# Main.net
KiCad netlist of a schematic drawn in Altium Designer
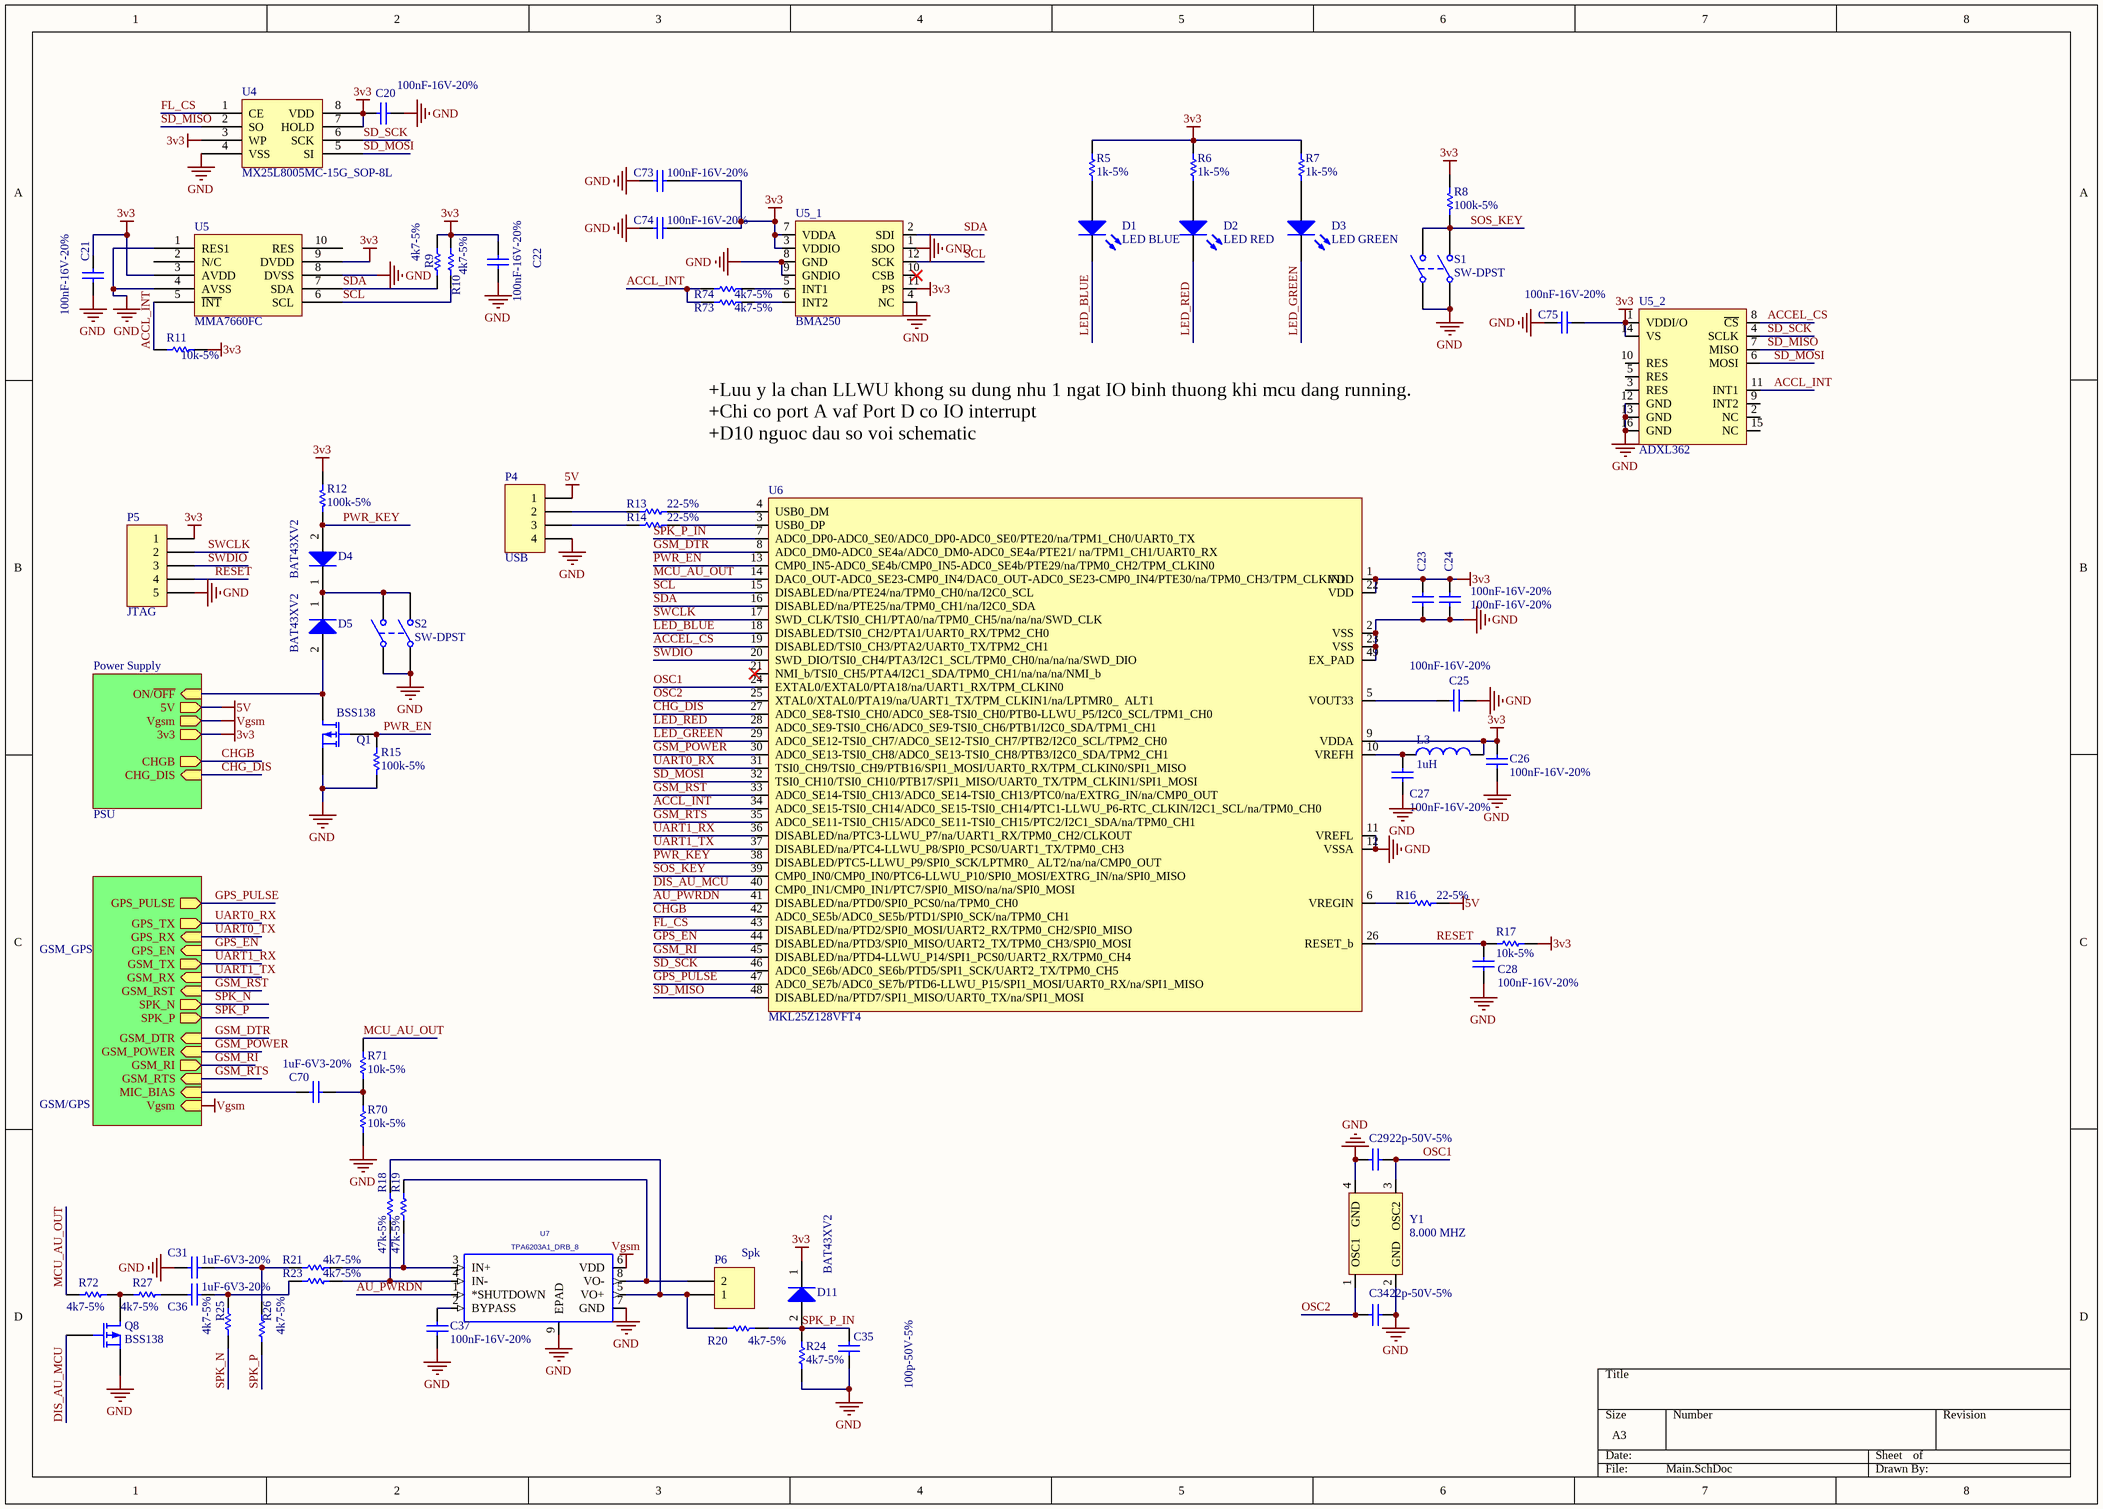
[diagram p0: Main.SchDoc]

(export (version "E")
  (design (tool "Eeschema 10.0.6"))
  (components
    (comp (ref "C20")
      (value "100nF-16V-20%")
      (footprint "C0402")
      (description "CAP CER 0.1UF 16V Y5V 0402")
      (fields
        (field (name "MANUFACTURER") "Yageo")
        (field (name "DIGI-KEY PART NUMBER") "311-1047-1-ND")
        (field (name "PUBLISHER") "Altium Limited")
      )
      (libsource (lib "Miscellaneous Devices") (part "Cap"))
    )
    (comp (ref "C21")
      (value "100nF-16V-20%")
      (footprint "C0402")
      (description "CAP CER 0.1UF 16V Y5V 0402")
      (fields
        (field (name "MANUFACTURER") "Yageo")
        (field (name "DIGI-KEY PART NUMBER") "311-1047-1-ND")
        (field (name "PUBLISHER") "Altium Limited")
      )
      (libsource (lib "Miscellaneous Devices") (part "Cap"))
    )
    (comp (ref "C22")
      (value "100nF-16V-20%")
      (footprint "C0402")
      (description "CAP CER 0.1UF 16V Y5V 0402")
      (fields
        (field (name "MANUFACTURER") "Yageo")
        (field (name "DIGI-KEY PART NUMBER") "311-1047-1-ND")
        (field (name "PUBLISHER") "Altium Limited")
      )
      (libsource (lib "Miscellaneous Devices") (part "Cap"))
    )
    (comp (ref "C23")
      (value "100nF-16V-20%")
      (footprint "C0402")
      (description "CAP CER 0.1UF 16V Y5V 0402")
      (fields
        (field (name "MANUFACTURER") "Yageo")
        (field (name "DIGI-KEY PART NUMBER") "311-1047-1-ND")
        (field (name "PUBLISHER") "Altium Limited")
      )
      (libsource (lib "Miscellaneous Devices") (part "Cap"))
    )
    (comp (ref "C24")
      (value "100nF-16V-20%")
      (footprint "C0402")
      (description "CAP CER 0.1UF 16V Y5V 0402")
      (fields
        (field (name "MANUFACTURER") "Yageo")
        (field (name "DIGI-KEY PART NUMBER") "311-1047-1-ND")
        (field (name "PUBLISHER") "Altium Limited")
      )
      (libsource (lib "Miscellaneous Devices") (part "Cap"))
    )
    (comp (ref "C25")
      (value "100nF-16V-20%")
      (footprint "C0402")
      (description "CAP CER 0.1UF 16V Y5V 0402")
      (fields
        (field (name "MANUFACTURER") "Yageo")
        (field (name "DIGI-KEY PART NUMBER") "311-1047-1-ND")
        (field (name "PUBLISHER") "Altium Limited")
      )
      (libsource (lib "Miscellaneous Devices") (part "Cap"))
    )
    (comp (ref "C26")
      (value "100nF-16V-20%")
      (footprint "C0402")
      (description "CAP CER 0.1UF 16V Y5V 0402")
      (fields
        (field (name "MANUFACTURER") "Yageo")
        (field (name "DIGI-KEY PART NUMBER") "311-1047-1-ND")
        (field (name "PUBLISHER") "Altium Limited")
      )
      (libsource (lib "Miscellaneous Devices") (part "Cap"))
    )
    (comp (ref "C27")
      (value "100nF-16V-20%")
      (footprint "C0402")
      (description "CAP CER 0.1UF 16V Y5V 0402")
      (fields
        (field (name "MANUFACTURER") "Yageo")
        (field (name "DIGI-KEY PART NUMBER") "311-1047-1-ND")
        (field (name "PUBLISHER") "Altium Limited")
      )
      (libsource (lib "Miscellaneous Devices") (part "Cap"))
    )
    (comp (ref "C28")
      (value "100nF-16V-20%")
      (footprint "C0402")
      (description "CAP CER 0.1UF 16V Y5V 0402")
      (fields
        (field (name "MANUFACTURER") "Yageo")
        (field (name "DIGI-KEY PART NUMBER") "311-1047-1-ND")
        (field (name "PUBLISHER") "Altium Limited")
      )
      (libsource (lib "Miscellaneous Devices") (part "Cap"))
    )
    (comp (ref "C29")
      (value "22p-50V-5%")
      (footprint "C0402")
      (description "CAP CER 22PF 50V 5% NPO 0402")
      (fields
        (field (name "MANUFACTURER") "Yageo")
        (field (name "DIGI-KEY PART NUMBER") "311-1018-2-ND")
        (field (name "PUBLISHER") "Altium Limited")
      )
      (libsource (lib "Miscellaneous Devices") (part "Cap"))
    )
    (comp (ref "C31")
      (value "1uF-6V3-20%")
      (footprint "C0402")
      (description "CAP CER 1UF 6.3V Y5V 0402")
      (fields
        (field (name "MANUFACTURER") "Yageo")
        (field (name "DIGI-KEY PART NUMBER") "311-1377-2-ND")
        (field (name "PUBLISHER") "Altium Limited")
      )
      (libsource (lib "Miscellaneous Devices") (part "Cap"))
    )
    (comp (ref "C34")
      (value "22p-50V-5%")
      (footprint "C0402")
      (description "CAP CER 22PF 50V 5% NPO 0402")
      (fields
        (field (name "MANUFACTURER") "Yageo")
        (field (name "DIGI-KEY PART NUMBER") "311-1018-2-ND")
        (field (name "PUBLISHER") "Altium Limited")
      )
      (libsource (lib "Miscellaneous Devices") (part "Cap"))
    )
    (comp (ref "C35")
      (value "100p-50V-5%")
      (footprint "C0402")
      (description "CAP CER 100PF 50V 5% NPO 0402")
      (fields
        (field (name "MANUFACTURER") "Yageo")
        (field (name "DIGI-KEY PART NUMBER") "311-1024-2-ND")
        (field (name "PUBLISHER") "Altium Limited")
      )
      (libsource (lib "Miscellaneous Devices") (part "Cap"))
    )
    (comp (ref "C36")
      (value "1uF-6V3-20%")
      (footprint "C0402")
      (description "CAP CER 1UF 6.3V Y5V 0402")
      (fields
        (field (name "MANUFACTURER") "Yageo")
        (field (name "DIGI-KEY PART NUMBER") "311-1377-2-ND")
        (field (name "PUBLISHER") "Altium Limited")
      )
      (libsource (lib "Miscellaneous Devices") (part "Cap"))
    )
    (comp (ref "C37")
      (value "100nF-16V-20%")
      (footprint "C0402")
      (description "CAP CER 0.1UF 16V Y5V 0402")
      (fields
        (field (name "MANUFACTURER") "Yageo")
        (field (name "DIGI-KEY PART NUMBER") "311-1047-1-ND")
        (field (name "PUBLISHER") "Altium Limited")
      )
      (libsource (lib "Miscellaneous Devices") (part "Cap"))
    )
    (comp (ref "C70")
      (value "1uF-6V3-20%")
      (footprint "C0402")
      (description "CAP CER 1UF 6.3V Y5V 0402")
      (fields
        (field (name "MANUFACTURER") "Yageo")
        (field (name "DIGI-KEY PART NUMBER") "311-1377-2-ND")
        (field (name "PUBLISHER") "Altium Limited")
      )
      (libsource (lib "Miscellaneous Devices") (part "Cap"))
    )
    (comp (ref "C73")
      (value "100nF-16V-20%")
      (footprint "C0402")
      (description "CAP CER 0.1UF 16V Y5V 0402")
      (fields
        (field (name "MANUFACTURER") "Yageo")
        (field (name "DIGI-KEY PART NUMBER") "311-1047-1-ND")
        (field (name "PUBLISHER") "Altium Limited")
      )
      (libsource (lib "Miscellaneous Devices") (part "Cap"))
    )
    (comp (ref "C74")
      (value "100nF-16V-20%")
      (footprint "C0402")
      (description "CAP CER 0.1UF 16V Y5V 0402")
      (fields
        (field (name "MANUFACTURER") "Yageo")
        (field (name "DIGI-KEY PART NUMBER") "311-1047-1-ND")
        (field (name "PUBLISHER") "Altium Limited")
      )
      (libsource (lib "Miscellaneous Devices") (part "Cap"))
    )
    (comp (ref "C75")
      (value "100nF-16V-20%")
      (footprint "C0402")
      (description "CAP CER 0.1UF 16V Y5V 0402")
      (fields
        (field (name "MANUFACTURER") "Yageo")
        (field (name "DIGI-KEY PART NUMBER") "311-1047-1-ND")
        (field (name "PUBLISHER") "Altium Limited")
      )
      (libsource (lib "Miscellaneous Devices") (part "Cap"))
    )
    (comp (ref "D1")
      (value "LED BLUE")
      (footprint "LED0603-G")
      (description "LED BLUE CLEAR THIN 0603 SMD")
      (fields
        (field (name "DIGI-KEY PART NUMBER") "160-1446-2-ND")
        (field (name "MANUFACTURER") "Lite-On Inc")
        (field (name "PUBLISHER") "Altium Limited")
      )
      (libsource (lib "Miscellaneous Devices") (part "LED2"))
    )
    (comp (ref "D2")
      (value "LED RED")
      (footprint "LED0603-G")
      (description "LED RED CLEAR THIN 0603 SMD")
      (fields
        (field (name "DIGI-KEY PART NUMBER") "160-1446-2-ND")
        (field (name "MANUFACTURER") "Lite-On Inc")
        (field (name "PUBLISHER") "Altium Limited")
      )
      (libsource (lib "Miscellaneous Devices") (part "LED2"))
    )
    (comp (ref "D3")
      (value "LED GREEN")
      (footprint "LED0603-G")
      (description "LED GREEN CLEAR THIN 0603 SMD")
      (fields
        (field (name "DIGI-KEY PART NUMBER") "160-1446-2-ND")
        (field (name "MANUFACTURER") "Lite-On Inc")
        (field (name "PUBLISHER") "Altium Limited")
      )
      (libsource (lib "Miscellaneous Devices") (part "LED2"))
    )
    (comp (ref "D4")
      (value "BAT43XV2")
      (footprint "SOD-523F")
      (description "Diode Type SMD")
      (fields
        (field (name "DIGI-KEY PART NUMBER") "BAT43XV2CT-ND")
        (field (name "MANUFACTURER") "Fairchild Semiconductor")
        (field (name "PUBLISHER") "Altium Limited")
      )
      (libsource (lib "Miscellaneous Devices") (part "Diode"))
    )
    (comp (ref "D5")
      (value "BAT43XV2")
      (footprint "SOD-523F")
      (description "Diode Type SMD")
      (fields
        (field (name "DIGI-KEY PART NUMBER") "BAT43XV2CT-ND")
        (field (name "MANUFACTURER") "Fairchild Semiconductor")
        (field (name "PUBLISHER") "Altium Limited")
      )
      (libsource (lib "Miscellaneous Devices") (part "Diode"))
    )
    (comp (ref "D11")
      (value "BAT43XV2")
      (footprint "SOD-523F")
      (description "Diode Type SMD")
      (fields
        (field (name "DIGI-KEY PART NUMBER") "BAT43XV2CT-ND")
        (field (name "MANUFACTURER") "Fairchild Semiconductor")
        (field (name "PUBLISHER") "Altium Limited")
      )
      (libsource (lib "Miscellaneous Devices") (part "Diode"))
    )
    (comp (ref "L3")
      (value "1uH")
      (footprint "L0603")
      (description "INDUCTOR 1.0UH 150MA 0603")
      (fields
        (field (name "DIGI-KEY PART NUMBER") "490-4022-2-ND")
        (field (name "MANUFACTURER") "Murata Electronics North America")
        (field (name "PUBLISHER") "Altium Limited")
      )
      (libsource (lib "Miscellaneous Devices") (part "Inductor"))
    )
    (comp (ref "P4")
      (value "USB")
      (footprint "GT102x_Housing_USB_nnector")
      (description "Header, 4-Pin")
      (fields (field (name "PUBLISHER") "Altium Limited"))
      (libsource (lib "Miscellaneous Connectors") (part "Header 4"))
    )
    (comp (ref "P5")
      (value "JTAG")
      (footprint "HEADER_1.27mm_5PIN")
      (description "Header, 5-Pin")
      (fields (field (name "PUBLISHER") "Altium Limited"))
      (libsource (lib "Miscellaneous Connectors") (part "Header 5"))
    )
    (comp (ref "P6")
      (value "Spk")
      (footprint "SPEAKER-S12A28")
      (description "Header, 2-Pin")
      (fields (field (name "PUBLISHER") "Altium Limited"))
      (libsource (lib "Miscellaneous Connectors") (part "Header 2"))
    )
    (comp (ref "Q1")
      (value "BSS138")
      (footprint "SOT23-3")
      (description "MOSFET N-CH 50V 200MA SOT23-3")
      (fields
        (field (name "DIGI-KEY PART NUMBER") "BSS138-FDICT-ND")
        (field (name "MANUFACTURER") "Diodes Inc")
        (field (name "PUBLISHER") "Altium Limited")
      )
      (libsource (lib "Miscellaneous Devices") (part "MOSFET-P"))
    )
    (comp (ref "Q8")
      (value "BSS138")
      (footprint "SOT23-3")
      (description "MOSFET N-CH 50V 200MA SOT23-3")
      (fields
        (field (name "DIGI-KEY PART NUMBER") "BSS138-FDICT-ND")
        (field (name "MANUFACTURER") "Diodes Inc")
        (field (name "PUBLISHER") "Altium Limited")
      )
      (libsource (lib "Miscellaneous Devices") (part "MOSFET-P"))
    )
    (comp (ref "R5")
      (value "1k-5%")
      (footprint "R0402")
      (description "RES 1.0K OHM 1/16W 5% 0402 SMD")
      (fields
        (field (name "DIGI-KEY PART NUMBER") "311-1.0KJRCT-ND")
        (field (name "MANUFACTURER") "Yageo")
        (field (name "PUBLISHER") "Altium Limited")
      )
      (libsource (lib "Miscellaneous Devices") (part "Res1"))
    )
    (comp (ref "R6")
      (value "1k-5%")
      (footprint "R0402")
      (description "RES 1.0K OHM 1/16W 5% 0402 SMD")
      (fields
        (field (name "DIGI-KEY PART NUMBER") "311-1.0KJRCT-ND")
        (field (name "MANUFACTURER") "Yageo")
        (field (name "PUBLISHER") "Altium Limited")
      )
      (libsource (lib "Miscellaneous Devices") (part "Res1"))
    )
    (comp (ref "R7")
      (value "1k-5%")
      (footprint "R0402")
      (description "RES 1.0K OHM 1/16W 5% 0402 SMD")
      (fields
        (field (name "DIGI-KEY PART NUMBER") "311-1.0KJRCT-ND")
        (field (name "MANUFACTURER") "Yageo")
        (field (name "PUBLISHER") "Altium Limited")
      )
      (libsource (lib "Miscellaneous Devices") (part "Res1"))
    )
    (comp (ref "R8")
      (value "100k-5%")
      (footprint "R0402")
      (description "RES 100K OHM 1/16W 5% 0402 SMD")
      (fields
        (field (name "DIGI-KEY PART NUMBER") "311-100KJRCT-ND")
        (field (name "MANUFACTURER") "Yageo")
        (field (name "PUBLISHER") "Altium Limited")
      )
      (libsource (lib "Miscellaneous Devices") (part "Res1"))
    )
    (comp (ref "R9")
      (value "4k7-5%")
      (footprint "R0402")
      (description "RES 4.7K OHM 1/16W 5% 0402 SMD")
      (fields
        (field (name "DIGI-KEY PART NUMBER") "311-4.7KJRCT-ND")
        (field (name "MANUFACTURER") "Yageo")
        (field (name "PUBLISHER") "Altium Limited")
      )
      (libsource (lib "Miscellaneous Devices") (part "Res1"))
    )
    (comp (ref "R10")
      (value "4k7-5%")
      (footprint "R0402")
      (description "RES 4.7K OHM 1/16W 5% 0402 SMD")
      (fields
        (field (name "DIGI-KEY PART NUMBER") "311-4.7KJRCT-ND")
        (field (name "MANUFACTURER") "Yageo")
        (field (name "PUBLISHER") "Altium Limited")
      )
      (libsource (lib "Miscellaneous Devices") (part "Res1"))
    )
    (comp (ref "R11")
      (value "10k-5%")
      (footprint "R0402")
      (description "RES 10K OHM 1/16W 5% 0402 SMD")
      (fields
        (field (name "DIGI-KEY PART NUMBER") "311-10KJRCT-ND")
        (field (name "MANUFACTURER") "Yageo")
        (field (name "PUBLISHER") "Altium Limited")
      )
      (libsource (lib "Miscellaneous Devices") (part "Res1"))
    )
    (comp (ref "R12")
      (value "100k-5%")
      (footprint "R0402")
      (description "RES 100K OHM 1/16W 5% 0402 SMD")
      (fields
        (field (name "DIGI-KEY PART NUMBER") "311-100KJRCT-ND")
        (field (name "MANUFACTURER") "Yageo")
        (field (name "PUBLISHER") "Altium Limited")
      )
      (libsource (lib "Miscellaneous Devices") (part "Res1"))
    )
    (comp (ref "R13")
      (value "22-5%")
      (footprint "R0402")
      (description "RES 22 OHM 1/16W 5% 0402 SMD")
      (fields
        (field (name "DIGI-KEY PART NUMBER") "311-22JRCT-ND")
        (field (name "MANUFACTURER") "Yageo")
        (field (name "PUBLISHER") "Altium Limited")
      )
      (libsource (lib "Miscellaneous Devices") (part "Res1"))
    )
    (comp (ref "R14")
      (value "22-5%")
      (footprint "R0402")
      (description "RES 22 OHM 1/16W 5% 0402 SMD")
      (fields
        (field (name "DIGI-KEY PART NUMBER") "311-22JRCT-ND")
        (field (name "MANUFACTURER") "Yageo")
        (field (name "PUBLISHER") "Altium Limited")
      )
      (libsource (lib "Miscellaneous Devices") (part "Res1"))
    )
    (comp (ref "R15")
      (value "100k-5%")
      (footprint "R0402")
      (description "RES 100K OHM 1/16W 5% 0402 SMD")
      (fields
        (field (name "DIGI-KEY PART NUMBER") "311-100KJRCT-ND")
        (field (name "MANUFACTURER") "Yageo")
        (field (name "PUBLISHER") "Altium Limited")
      )
      (libsource (lib "Miscellaneous Devices") (part "Res1"))
    )
    (comp (ref "R16")
      (value "22-5%")
      (footprint "R0402")
      (description "RES 22 OHM 1/16W 5% 0402 SMD")
      (fields
        (field (name "DIGI-KEY PART NUMBER") "311-22JRCT-ND")
        (field (name "MANUFACTURER") "Yageo")
        (field (name "PUBLISHER") "Altium Limited")
      )
      (libsource (lib "Miscellaneous Devices") (part "Res1"))
    )
    (comp (ref "R17")
      (value "10k-5%")
      (footprint "R0402")
      (description "RES 10K OHM 1/16W 5% 0402 SMD")
      (fields
        (field (name "DIGI-KEY PART NUMBER") "311-10KJRCT-ND")
        (field (name "MANUFACTURER") "Yageo")
        (field (name "PUBLISHER") "Altium Limited")
      )
      (libsource (lib "Miscellaneous Devices") (part "Res1"))
    )
    (comp (ref "R18")
      (value "47k-5%")
      (footprint "R0402")
      (description "RES 47K OHM 1/16W 5% 0402 SMD")
      (fields
        (field (name "DIGI-KEY PART NUMBER") "311-47KJRCT-ND")
        (field (name "MANUFACTURER") "Yageo")
        (field (name "PUBLISHER") "Altium Limited")
      )
      (libsource (lib "Miscellaneous Devices") (part "Res1"))
    )
    (comp (ref "R19")
      (value "47k-5%")
      (footprint "R0402")
      (description "RES 47K OHM 1/16W 5% 0402 SMD")
      (fields
        (field (name "DIGI-KEY PART NUMBER") "311-47KJRCT-ND")
        (field (name "MANUFACTURER") "Yageo")
        (field (name "PUBLISHER") "Altium Limited")
      )
      (libsource (lib "Miscellaneous Devices") (part "Res1"))
    )
    (comp (ref "R20")
      (value "4k7-5%")
      (footprint "R0402")
      (description "RES 4.7K OHM 1/16W 5% 0402 SMD")
      (fields
        (field (name "DIGI-KEY PART NUMBER") "311-4.7KJRCT-ND")
        (field (name "MANUFACTURER") "Yageo")
        (field (name "PUBLISHER") "Altium Limited")
      )
      (libsource (lib "Miscellaneous Devices") (part "Res1"))
    )
    (comp (ref "R21")
      (value "4k7-5%")
      (footprint "R0402")
      (description "RES 4.7K OHM 1/16W 5% 0402 SMD")
      (fields
        (field (name "DIGI-KEY PART NUMBER") "311-4.7KJRCT-ND")
        (field (name "MANUFACTURER") "Yageo")
        (field (name "PUBLISHER") "Altium Limited")
      )
      (libsource (lib "Miscellaneous Devices") (part "Res1"))
    )
    (comp (ref "R23")
      (value "4k7-5%")
      (footprint "R0402")
      (description "RES 4.7K OHM 1/16W 5% 0402 SMD")
      (fields
        (field (name "DIGI-KEY PART NUMBER") "311-4.7KJRCT-ND")
        (field (name "MANUFACTURER") "Yageo")
        (field (name "PUBLISHER") "Altium Limited")
      )
      (libsource (lib "Miscellaneous Devices") (part "Res1"))
    )
    (comp (ref "R24")
      (value "4k7-5%")
      (footprint "R0402")
      (description "RES 4.7K OHM 1/16W 5% 0402 SMD")
      (fields
        (field (name "DIGI-KEY PART NUMBER") "311-4.7KJRCT-ND")
        (field (name "MANUFACTURER") "Yageo")
        (field (name "PUBLISHER") "Altium Limited")
      )
      (libsource (lib "Miscellaneous Devices") (part "Res1"))
    )
    (comp (ref "R25")
      (value "4k7-5%")
      (footprint "R0402")
      (description "RES 4.7K OHM 1/16W 5% 0402 SMD")
      (fields
        (field (name "DIGI-KEY PART NUMBER") "311-4.7KJRCT-ND")
        (field (name "MANUFACTURER") "Yageo")
        (field (name "PUBLISHER") "Altium Limited")
      )
      (libsource (lib "Miscellaneous Devices") (part "Res1"))
    )
    (comp (ref "R26")
      (value "4k7-5%")
      (footprint "R0402")
      (description "RES 4.7K OHM 1/16W 5% 0402 SMD")
      (fields
        (field (name "DIGI-KEY PART NUMBER") "311-4.7KJRCT-ND")
        (field (name "MANUFACTURER") "Yageo")
        (field (name "PUBLISHER") "Altium Limited")
      )
      (libsource (lib "Miscellaneous Devices") (part "Res1"))
    )
    (comp (ref "R27")
      (value "4k7-5%")
      (footprint "R0402")
      (description "RES 4.7K OHM 1/16W 5% 0402 SMD")
      (fields
        (field (name "DIGI-KEY PART NUMBER") "311-4.7KJRCT-ND")
        (field (name "MANUFACTURER") "Yageo")
        (field (name "PUBLISHER") "Altium Limited")
      )
      (libsource (lib "Miscellaneous Devices") (part "Res1"))
    )
    (comp (ref "R70")
      (value "10k-5%")
      (footprint "R0402")
      (description "RES 10K OHM 1/16W 5% 0402 SMD")
      (fields
        (field (name "DIGI-KEY PART NUMBER") "311-10KJRCT-ND")
        (field (name "MANUFACTURER") "Yageo")
        (field (name "PUBLISHER") "Altium Limited")
      )
      (libsource (lib "Miscellaneous Devices") (part "Res1"))
    )
    (comp (ref "R71")
      (value "10k-5%")
      (footprint "R0402")
      (description "RES 10K OHM 1/16W 5% 0402 SMD")
      (fields
        (field (name "DIGI-KEY PART NUMBER") "311-10KJRCT-ND")
        (field (name "MANUFACTURER") "Yageo")
        (field (name "PUBLISHER") "Altium Limited")
      )
      (libsource (lib "Miscellaneous Devices") (part "Res1"))
    )
    (comp (ref "R72")
      (value "4k7-5%")
      (footprint "R0402")
      (description "RES 4.7K OHM 1/16W 5% 0402 SMD")
      (fields
        (field (name "DIGI-KEY PART NUMBER") "311-4.7KJRCT-ND")
        (field (name "MANUFACTURER") "Yageo")
        (field (name "PUBLISHER") "Altium Limited")
      )
      (libsource (lib "Miscellaneous Devices") (part "Res1"))
    )
    (comp (ref "R73")
      (value "4k7-5%")
      (footprint "R0402")
      (description "RES 4.7K OHM 1/16W 5% 0402 SMD")
      (fields
        (field (name "DIGI-KEY PART NUMBER") "311-4.7KJRCT-ND")
        (field (name "MANUFACTURER") "Yageo")
        (field (name "PUBLISHER") "Altium Limited")
      )
      (libsource (lib "Miscellaneous Devices") (part "Res1"))
    )
    (comp (ref "R74")
      (value "4k7-5%")
      (footprint "R0402")
      (description "RES 4.7K OHM 1/16W 5% 0402 SMD")
      (fields
        (field (name "DIGI-KEY PART NUMBER") "311-4.7KJRCT-ND")
        (field (name "MANUFACTURER") "Yageo")
        (field (name "PUBLISHER") "Altium Limited")
      )
      (libsource (lib "Miscellaneous Devices") (part "Res1"))
    )
    (comp (ref "S1")
      (value "SW-DPST")
      (footprint "BUTTON-TVAF11-025B-R")
      (description "Double-Pole, Single-Throw Switch")
      (fields (field (name "PUBLISHER") "Altium Limited"))
      (libsource (lib "Miscellaneous Devices") (part "SW-DPST"))
    )
    (comp (ref "S2")
      (value "SW-DPST")
      (footprint "BUTTON-TVAF11-025B-R")
      (description "Double-Pole, Single-Throw Switch")
      (fields (field (name "PUBLISHER") "Altium Limited"))
      (libsource (lib "Miscellaneous Devices") (part "SW-DPST"))
    )
    (comp (ref "U4")
      (value "MX25L8005MC-15G_SOP-8L")
      (footprint "SO8-150mil")
      (fields (field (name "MANUFACTURER") "Tyrone"))
      (libsource (lib "My LB") (part "FlashIC"))
    )
    (comp (ref "U5")
      (value "MMA7660FC")
      (footprint "MMA7660FC")
      (description "ACCELEROMETER 3X3 DGTL 10-DFN")
      (fields
        (field (name "DIGI-KEY PART NUMBER") "MMA7660FCT-ND")
        (field (name "MANUFACTURER") "Freescale Semiconductor")
      )
      (libsource (lib "Lib") (part "MMA7660FC"))
    )
    (comp (ref "U5_1")
      (value "BMA250")
      (footprint "BMA250")
      (description "3-AXIS ACCELEROMETER DIGITAL I/F")
      (libsource (lib "Lib") (part "BMA250"))
    )
    (comp (ref "U5_2")
      (value "ADXL362")
      (footprint "ADXL362")
      (description "IC ACCEL DIG LO PWR 3AX 16LGA")
      (fields
        (field (name "DIGI-KEY PART NUMBER") "ADXL362BCCZ-R2CT-ND")
        (field (name "MANUFACTURER PART NUMBER") "ADXL362BCCZ-RL7")
      )
      (libsource (lib "Lib") (part "ADCL362"))
    )
    (comp (ref "U6")
      (value "MKL25Z128VFT4")
      (description "IC ARM CORTEX MCU 128KB 48QFN")
      (fields
        (field (name "DIGI-KEY PART NUMBER") "MKL25Z128VFT4-ND")
        (field (name "MANUFACTURER") "Freescale Semiconductor")
      )
      (libsource (lib "freescale_MCU") (part "MKL25Z128VFT4"))
    )
    (comp (ref "U7")
      (value "TPA6203A1_DRB_8")
      (footprint "DRB8_1P75X1P5")
      (description "IC AMP AUDIO PWR 1.25W MONO 8SON")
      (fields
        (field (name "MANUFACTURER PART NUMBER") "TPA6203A1DRB")
        (field (name "GENERIC_PART_NUMBER") "TPA6203A1")
      )
      (libsource (lib "TI_Audio") (part "TPA6203A1_DRB_8"))
    )
    (comp (ref "Y1")
      (value "8.000 MHZ")
      (footprint "SMD CRYSTAL 4 x 2.5")
      (description "CRYSTAL 8.000 MHZ 18PF SMD")
      (fields
        (field (name "DIGI-KEY PART NUMBER") "887-1452-2-ND")
        (field (name "MANUFACTURER") "TXC CORPORATION")
      )
      (libsource (lib "Schlib1") (part "CRYSTAL-SMT"))
    )
  )
  (nets
    (net (code "1") (name "/ACCEL_CS") (class "Default")
      (node (ref "U5_2") (pin "8") (pinfunction "~{CS}_8") (pintype "passive"))
      (node (ref "U6") (pin "19") (pinfunction "DISABLED/TSI0_CH3/PTA2/UART0_TX/TPM2_CH1_19") (pintype "passive"))
    )
    (net (code "2") (name "/ACCL_INT") (class "Default")
      (node (ref "R11") (pin "1") (pinfunction "1_1") (pintype "passive"))
      (node (ref "R73") (pin "2") (pinfunction "2_2") (pintype "passive"))
      (node (ref "R74") (pin "2") (pinfunction "2_2") (pintype "passive"))
      (node (ref "U5") (pin "5") (pinfunction "~{INT}_5") (pintype "passive"))
      (node (ref "U5_2") (pin "11") (pinfunction "INT1_11") (pintype "passive"))
      (node (ref "U6") (pin "34") (pinfunction "ADC0_SE15-TSI0_CH14/ADC0_SE15-TSI0_CH14/PTC1-LLWU_P6-RTC_CLKIN/I2C1_SCL/na/TPM0_CH0_34") (pintype "passive"))
    )
    (net (code "3") (name "/AU_PWRDN") (class "Default")
      (node (ref "U6") (pin "41") (pinfunction "DISABLED/na/PTD0/SPI0_PCS0/na/TPM0_CH0_41") (pintype "passive"))
      (node (ref "U7") (pin "1") (pinfunction "*SHUTDOWN_1") (pintype "input"))
    )
    (net (code "4") (name "/CHGB") (class "Default")
      (node (ref "U6") (pin "42") (pinfunction "ADC0_SE5b/ADC0_SE5b/PTD1/SPI0_SCK/na/TPM0_CH1_42") (pintype "passive"))
    )
    (net (code "5") (name "/CHG_DIS") (class "Default")
      (node (ref "U6") (pin "27") (pinfunction "ADC0_SE8-TSI0_CH0/ADC0_SE8-TSI0_CH0/PTB0-LLWU_P5/I2C0_SCL/TPM1_CH0_27") (pintype "passive"))
    )
    (net (code "6") (name "/DIS_AU_MCU") (class "Default")
      (node (ref "Q8") (pin "1") (pinfunction "G_1") (pintype "passive"))
      (node (ref "U6") (pin "40") (pinfunction "CMP0_IN1/CMP0_IN1/PTC7/SPI0_MISO/na/na/SPI0_MOSI_40") (pintype "passive"))
    )
    (net (code "7") (name "/FL_CS") (class "Default")
      (node (ref "U4") (pin "1") (pinfunction "CE_1") (pintype "passive"))
      (node (ref "U6") (pin "43") (pinfunction "DISABLED/na/PTD2/SPI0_MOSI/UART2_RX/TPM0_CH2/SPI0_MISO_43") (pintype "passive"))
    )
    (net (code "8") (name "/GPS_EN") (class "Default")
      (node (ref "U6") (pin "44") (pinfunction "DISABLED/na/PTD3/SPI0_MISO/UART2_TX/TPM0_CH3/SPI0_MOSI_44") (pintype "passive"))
    )
    (net (code "9") (name "/GPS_PULSE") (class "Default")
      (node (ref "U6") (pin "47") (pinfunction "ADC0_SE7b/ADC0_SE7b/PTD6-LLWU_P15/SPI1_MOSI/UART0_RX/na/SPI1_MISO_47") (pintype "passive"))
    )
    (net (code "10") (name "/GSM_DTR") (class "Default")
      (node (ref "U6") (pin "8") (pinfunction "ADC0_DM0-ADC0_SE4a/ADC0_DM0-ADC0_SE4a/PTE21/_na/TPM1_CH1/UART0_RX_8") (pintype "passive"))
    )
    (net (code "11") (name "/GSM_POWER") (class "Default")
      (node (ref "U6") (pin "30") (pinfunction "ADC0_SE13-TSI0_CH8/ADC0_SE13-TSI0_CH8/PTB3/I2C0_SDA/TPM2_CH1_30") (pintype "passive"))
    )
    (net (code "12") (name "/GSM_RI") (class "Default")
      (node (ref "U6") (pin "45") (pinfunction "DISABLED/na/PTD4-LLWU_P14/SPI1_PCS0/UART2_RX/TPM0_CH4_45") (pintype "passive"))
    )
    (net (code "13") (name "/GSM_RST") (class "Default")
      (node (ref "U6") (pin "33") (pinfunction "ADC0_SE14-TSI0_CH13/ADC0_SE14-TSI0_CH13/PTC0/na/EXTRG_IN/na/CMP0_OUT_33") (pintype "passive"))
    )
    (net (code "14") (name "/GSM_RTS") (class "Default")
      (node (ref "U6") (pin "35") (pinfunction "ADC0_SE11-TSI0_CH15/ADC0_SE11-TSI0_CH15/PTC2/I2C1_SDA/na/TPM0_CH1_35") (pintype "passive"))
    )
    (net (code "15") (name "/LED_BLUE") (class "Default")
      (node (ref "D1") (pin "2") (pinfunction "K_2") (pintype "passive"))
      (node (ref "U6") (pin "18") (pinfunction "DISABLED/TSI0_CH2/PTA1/UART0_RX/TPM2_CH0_18") (pintype "passive"))
    )
    (net (code "16") (name "/LED_GREEN") (class "Default")
      (node (ref "D3") (pin "2") (pinfunction "K_2") (pintype "passive"))
      (node (ref "U6") (pin "29") (pinfunction "ADC0_SE12-TSI0_CH7/ADC0_SE12-TSI0_CH7/PTB2/I2C0_SCL/TPM2_CH0_29") (pintype "passive"))
    )
    (net (code "17") (name "/LED_RED") (class "Default")
      (node (ref "D2") (pin "2") (pinfunction "K_2") (pintype "passive"))
      (node (ref "U6") (pin "28") (pinfunction "ADC0_SE9-TSI0_CH6/ADC0_SE9-TSI0_CH6/PTB1/I2C0_SDA/TPM1_CH1_28") (pintype "passive"))
    )
    (net (code "18") (name "/MCU_AU_OUT") (class "Default")
      (node (ref "R71") (pin "2") (pinfunction "2_2") (pintype "passive"))
      (node (ref "R72") (pin "1") (pinfunction "1_1") (pintype "passive"))
      (node (ref "U6") (pin "14") (pinfunction "DAC0_OUT-ADC0_SE23-CMP0_IN4/DAC0_OUT-ADC0_SE23-CMP0_IN4/PTE30/na/TPM0_CH3/TPM_CLKIN1_14") (pintype "passive"))
    )
    (net (code "19") (name "/MIC_BIAS") (class "Default")
      (node (ref "C70") (pin "2") (pinfunction "2_2") (pintype "passive"))
    )
    (net (code "20") (name "/ON{slash}~{OFF}") (class "Default")
      (node (ref "D5") (pin "2") (pinfunction "A_2") (pintype "passive"))
      (node (ref "Q1") (pin "3") (pinfunction "D_3") (pintype "passive"))
    )
    (net (code "21") (name "/OSC1") (class "Default")
      (node (ref "C29") (pin "2") (pinfunction "2_2") (pintype "passive"))
      (node (ref "U6") (pin "24") (pinfunction "EXTAL0/EXTAL0/PTA18/na/UART1_RX/TPM_CLKIN0_24") (pintype "passive"))
      (node (ref "Y1") (pin "3") (pinfunction "OSC2_3") (pintype "passive"))
    )
    (net (code "22") (name "/OSC2") (class "Default")
      (node (ref "C34") (pin "1") (pinfunction "1_1") (pintype "passive"))
      (node (ref "U6") (pin "25") (pinfunction "XTAL0/XTAL0/PTA19/na/UART1_TX/TPM_CLKIN1/na/LPTMR0___ALT1_25") (pintype "passive"))
      (node (ref "Y1") (pin "1") (pinfunction "OSC1_1") (pintype "passive"))
    )
    (net (code "23") (name "/PWR_EN") (class "Default")
      (node (ref "Q1") (pin "1") (pinfunction "G_1") (pintype "passive"))
      (node (ref "R15") (pin "1") (pinfunction "1_1") (pintype "passive"))
      (node (ref "U6") (pin "13") (pinfunction "CMP0_IN5-ADC0_SE4b/CMP0_IN5-ADC0_SE4b/PTE29/na/TPM0_CH2/TPM_CLKIN0_13") (pintype "passive"))
    )
    (net (code "24") (name "/PWR_KEY") (class "Default")
      (node (ref "D4") (pin "2") (pinfunction "A_2") (pintype "passive"))
      (node (ref "R12") (pin "2") (pinfunction "2_2") (pintype "passive"))
      (node (ref "U6") (pin "38") (pinfunction "DISABLED/PTC5-LLWU_P9/SPI0_SCK/LPTMR0__ALT2/na/na/CMP0_OUT_38") (pintype "passive"))
    )
    (net (code "25") (name "/RESET") (class "Default")
      (node (ref "C28") (pin "2") (pinfunction "2_2") (pintype "passive"))
      (node (ref "P5") (pin "4") (pinfunction "4_4") (pintype "passive"))
      (node (ref "R17") (pin "1") (pinfunction "1_1") (pintype "passive"))
      (node (ref "U6") (pin "26") (pinfunction "RESET_b_26") (pintype "passive"))
    )
    (net (code "26") (name "/SCL") (class "Default")
      (node (ref "R10") (pin "1") (pinfunction "1_1") (pintype "passive"))
      (node (ref "U5") (pin "6") (pinfunction "SCL_6") (pintype "passive"))
      (node (ref "U5_1") (pin "12") (pinfunction "SCK_12") (pintype "passive"))
      (node (ref "U6") (pin "15") (pinfunction "DISABLED/na/PTE24/na/TPM0_CH0/na/I2C0_SCL_15") (pintype "passive"))
    )
    (net (code "27") (name "/SDA") (class "Default")
      (node (ref "R9") (pin "1") (pinfunction "1_1") (pintype "passive"))
      (node (ref "U5") (pin "7") (pinfunction "SDA_7") (pintype "passive"))
      (node (ref "U5_1") (pin "2") (pinfunction "SDI_2") (pintype "passive"))
      (node (ref "U6") (pin "16") (pinfunction "DISABLED/na/PTE25/na/TPM0_CH1/na/I2C0_SDA_16") (pintype "passive"))
    )
    (net (code "28") (name "/SD_MISO") (class "Default")
      (node (ref "U4") (pin "2") (pinfunction "SO_2") (pintype "passive"))
      (node (ref "U5_2") (pin "7") (pinfunction "MISO_7") (pintype "passive"))
      (node (ref "U6") (pin "48") (pinfunction "DISABLED/na/PTD7/SPI1_MISO/UART0_TX/na/SPI1_MOSI_48") (pintype "passive"))
    )
    (net (code "29") (name "/SD_MOSI") (class "Default")
      (node (ref "U4") (pin "5") (pinfunction "SI_5") (pintype "passive"))
      (node (ref "U5_2") (pin "6") (pinfunction "MOSI_6") (pintype "passive"))
      (node (ref "U6") (pin "32") (pinfunction "TSI0_CH10/TSI0_CH10/PTB17/SPI1_MISO/UART0_TX/TPM_CLKIN1/SPI1_MOSI_32") (pintype "passive"))
    )
    (net (code "30") (name "/SD_SCK") (class "Default")
      (node (ref "U4") (pin "6") (pinfunction "SCK_6") (pintype "passive"))
      (node (ref "U5_2") (pin "4") (pinfunction "SCLK_4") (pintype "passive"))
      (node (ref "U6") (pin "46") (pinfunction "ADC0_SE6b/ADC0_SE6b/PTD5/SPI1_SCK/UART2_TX/TPM0_CH5_46") (pintype "passive"))
    )
    (net (code "31") (name "/SOS_KEY") (class "Default")
      (node (ref "R8") (pin "2") (pinfunction "2_2") (pintype "passive"))
      (node (ref "S1") (pin "3") (pinfunction "3_3") (pintype "passive"))
      (node (ref "S1") (pin "4") (pinfunction "4_4") (pintype "passive"))
      (node (ref "U6") (pin "39") (pinfunction "CMP0_IN0/CMP0_IN0/PTC6-LLWU_P10/SPI0_MOSI/EXTRG_IN/na/SPI0_MISO_39") (pintype "passive"))
    )
    (net (code "32") (name "/SPK_N") (class "Default")
      (node (ref "R25") (pin "2") (pinfunction "2_2") (pintype "passive"))
    )
    (net (code "33") (name "/SPK_P") (class "Default")
      (node (ref "R26") (pin "2") (pinfunction "2_2") (pintype "passive"))
    )
    (net (code "34") (name "/SPK_P_IN") (class "Default")
      (node (ref "C35") (pin "2") (pinfunction "2_2") (pintype "passive"))
      (node (ref "D11") (pin "2") (pinfunction "A_2") (pintype "passive"))
      (node (ref "R20") (pin "1") (pinfunction "1_1") (pintype "passive"))
      (node (ref "R24") (pin "1") (pinfunction "1_1") (pintype "passive"))
      (node (ref "U6") (pin "7") (pinfunction "ADC0_DP0-ADC0_SE0/ADC0_DP0-ADC0_SE0/PTE20/na/TPM1_CH0/UART0_TX_7") (pintype "passive"))
    )
    (net (code "35") (name "/SWCLK") (class "Default")
      (node (ref "P5") (pin "2") (pinfunction "2_2") (pintype "passive"))
      (node (ref "U6") (pin "17") (pinfunction "SWD_CLK/TSI0_CH1/PTA0/na/TPM0_CH5/na/na/na/SWD_CLK_17") (pintype "passive"))
    )
    (net (code "36") (name "/SWDIO") (class "Default")
      (node (ref "P5") (pin "3") (pinfunction "3_3") (pintype "passive"))
      (node (ref "U6") (pin "20") (pinfunction "SWD_DIO/TSI0_CH4/PTA3/I2C1_SCL/TPM0_CH0/na/na/na/SWD_DIO_20") (pintype "passive"))
    )
    (net (code "37") (name "/UART0_RX") (class "Default")
      (node (ref "U6") (pin "31") (pinfunction "TSI0_CH9/TSI0_CH9/PTB16/SPI1_MOSI/UART0_RX/TPM_CLKIN0/SPI1_MISO_31") (pintype "passive"))
    )
    (net (code "39") (name "/UART1_RX") (class "Default")
      (node (ref "U6") (pin "36") (pinfunction "DISABLED/na/PTC3-LLWU_P7/na/UART1_RX/TPM0_CH2/CLKOUT_36") (pintype "passive"))
    )
    (net (code "40") (name "/UART1_TX") (class "Default")
      (node (ref "U6") (pin "37") (pinfunction "DISABLED/na/PTC4-LLWU_P8/SPI0_PCS0/UART1_TX/TPM0_CH3_37") (pintype "passive"))
    )
    (net (code "41") (name "3v3") (class "Default")
      (node (ref "C20") (pin "1") (pinfunction "1_1") (pintype "passive"))
      (node (ref "C21") (pin "2") (pinfunction "2_2") (pintype "passive"))
      (node (ref "C22") (pin "2") (pinfunction "2_2") (pintype "passive"))
      (node (ref "C23") (pin "1") (pinfunction "1_1") (pintype "passive"))
      (node (ref "C24") (pin "1") (pinfunction "1_1") (pintype "passive"))
      (node (ref "C26") (pin "2") (pinfunction "2_2") (pintype "passive"))
      (node (ref "C73") (pin "2") (pinfunction "2_2") (pintype "passive"))
      (node (ref "C74") (pin "2") (pinfunction "2_2") (pintype "passive"))
      (node (ref "C75") (pin "2") (pinfunction "2_2") (pintype "passive"))
      (node (ref "D11") (pin "1") (pinfunction "K_1") (pintype "passive"))
      (node (ref "L3") (pin "2") (pinfunction "2_2") (pintype "passive"))
      (node (ref "P5") (pin "1") (pinfunction "1_1") (pintype "passive"))
      (node (ref "R10") (pin "2") (pinfunction "2_2") (pintype "passive"))
      (node (ref "R11") (pin "2") (pinfunction "2_2") (pintype "passive"))
      (node (ref "R12") (pin "1") (pinfunction "1_1") (pintype "passive"))
      (node (ref "R17") (pin "2") (pinfunction "2_2") (pintype "passive"))
      (node (ref "R5") (pin "2") (pinfunction "2_2") (pintype "passive"))
      (node (ref "R6") (pin "2") (pinfunction "2_2") (pintype "passive"))
      (node (ref "R7") (pin "2") (pinfunction "2_2") (pintype "passive"))
      (node (ref "R8") (pin "1") (pinfunction "1_1") (pintype "passive"))
      (node (ref "R9") (pin "2") (pinfunction "2_2") (pintype "passive"))
      (node (ref "U4") (pin "3") (pinfunction "WP_3") (pintype "passive"))
      (node (ref "U4") (pin "7") (pinfunction "HOLD_7") (pintype "passive"))
      (node (ref "U4") (pin "8") (pinfunction "VDD_8") (pintype "passive"))
      (node (ref "U5") (pin "3") (pinfunction "AVDD_3") (pintype "passive"))
      (node (ref "U5") (pin "9") (pinfunction "DVDD_9") (pintype "passive"))
      (node (ref "U5_1") (pin "11") (pinfunction "PS_11") (pintype "passive"))
      (node (ref "U5_1") (pin "3") (pinfunction "VDDIO_3") (pintype "passive"))
      (node (ref "U5_1") (pin "7") (pinfunction "VDDA_7") (pintype "passive"))
      (node (ref "U5_2") (pin "1") (pinfunction "VDDI/O_1") (pintype "passive"))
      (node (ref "U5_2") (pin "14") (pinfunction "VS_14") (pintype "passive"))
      (node (ref "U6") (pin "1") (pinfunction "VDD_1") (pintype "passive"))
      (node (ref "U6") (pin "22") (pinfunction "VDD_22") (pintype "passive"))
      (node (ref "U6") (pin "9") (pinfunction "VDDA_9") (pintype "passive"))
    )
    (net (code "42") (name "5V") (class "Default")
      (node (ref "P4") (pin "1") (pinfunction "1_1") (pintype "passive"))
      (node (ref "R16") (pin "2") (pinfunction "2_2") (pintype "passive"))
    )
    (net (code "43") (name "GND") (class "Default")
      (node (ref "C20") (pin "2") (pinfunction "2_2") (pintype "passive"))
      (node (ref "C21") (pin "1") (pinfunction "1_1") (pintype "passive"))
      (node (ref "C22") (pin "1") (pinfunction "1_1") (pintype "passive"))
      (node (ref "C23") (pin "2") (pinfunction "2_2") (pintype "passive"))
      (node (ref "C24") (pin "2") (pinfunction "2_2") (pintype "passive"))
      (node (ref "C25") (pin "2") (pinfunction "2_2") (pintype "passive"))
      (node (ref "C26") (pin "1") (pinfunction "1_1") (pintype "passive"))
      (node (ref "C27") (pin "1") (pinfunction "1_1") (pintype "passive"))
      (node (ref "C28") (pin "1") (pinfunction "1_1") (pintype "passive"))
      (node (ref "C29") (pin "1") (pinfunction "1_1") (pintype "passive"))
      (node (ref "C31") (pin "2") (pinfunction "2_2") (pintype "passive"))
      (node (ref "C34") (pin "2") (pinfunction "2_2") (pintype "passive"))
      (node (ref "C35") (pin "1") (pinfunction "1_1") (pintype "passive"))
      (node (ref "C37") (pin "1") (pinfunction "1_1") (pintype "passive"))
      (node (ref "C73") (pin "1") (pinfunction "1_1") (pintype "passive"))
      (node (ref "C74") (pin "1") (pinfunction "1_1") (pintype "passive"))
      (node (ref "C75") (pin "1") (pinfunction "1_1") (pintype "passive"))
      (node (ref "P4") (pin "4") (pinfunction "4_4") (pintype "passive"))
      (node (ref "P5") (pin "5") (pinfunction "5_5") (pintype "passive"))
      (node (ref "Q1") (pin "2") (pinfunction "S_2") (pintype "passive"))
      (node (ref "Q8") (pin "2") (pinfunction "S_2") (pintype "passive"))
      (node (ref "R15") (pin "2") (pinfunction "2_2") (pintype "passive"))
      (node (ref "R24") (pin "2") (pinfunction "2_2") (pintype "passive"))
      (node (ref "R70") (pin "1") (pinfunction "1_1") (pintype "passive"))
      (node (ref "S1") (pin "1") (pinfunction "1_1") (pintype "passive"))
      (node (ref "S1") (pin "2") (pinfunction "2_2") (pintype "passive"))
      (node (ref "S2") (pin "1") (pinfunction "1_1") (pintype "passive"))
      (node (ref "S2") (pin "2") (pinfunction "2_2") (pintype "passive"))
      (node (ref "U4") (pin "4") (pinfunction "VSS_4") (pintype "passive"))
      (node (ref "U5") (pin "1") (pinfunction "RES1_1") (pintype "passive"))
      (node (ref "U5") (pin "4") (pinfunction "AVSS_4") (pintype "passive"))
      (node (ref "U5") (pin "8") (pinfunction "DVSS_8") (pintype "passive"))
      (node (ref "U5_1") (pin "1") (pinfunction "SDO_1") (pintype "passive"))
      (node (ref "U5_1") (pin "4") (pinfunction "NC_4") (pintype "passive"))
      (node (ref "U5_1") (pin "8") (pinfunction "GND_8") (pintype "passive"))
      (node (ref "U5_1") (pin "9") (pinfunction "GNDIO_9") (pintype "passive"))
      (node (ref "U5_2") (pin "12") (pinfunction "GND_12") (pintype "passive"))
      (node (ref "U5_2") (pin "13") (pinfunction "GND_13") (pintype "passive"))
      (node (ref "U5_2") (pin "16") (pinfunction "GND_16") (pintype "passive"))
      (node (ref "U6") (pin "11") (pinfunction "VREFL_11") (pintype "passive"))
      (node (ref "U6") (pin "12") (pinfunction "VSSA_12") (pintype "passive"))
      (node (ref "U6") (pin "2") (pinfunction "VSS_2") (pintype "passive"))
      (node (ref "U6") (pin "23") (pinfunction "VSS_23") (pintype "passive"))
      (node (ref "U6") (pin "49") (pinfunction "EX_PAD_49") (pintype "passive"))
      (node (ref "U7") (pin "7") (pinfunction "GND_7") (pintype "power_in"))
      (node (ref "U7") (pin "9") (pinfunction "EPAD_9") (pintype "passive"))
      (node (ref "Y1") (pin "2") (pinfunction "GND_2") (pintype "passive"))
      (node (ref "Y1") (pin "4") (pinfunction "GND_4") (pintype "passive"))
    )
    (net (code "44") (name "Net-(C31-Pad1)") (class "Default")
      (node (ref "C31") (pin "1") (pinfunction "1_1") (pintype "passive"))
      (node (ref "R21") (pin "2") (pinfunction "2_2") (pintype "passive"))
      (node (ref "R26") (pin "1") (pinfunction "1_1") (pintype "passive"))
    )
    (net (code "45") (name "Net-(C36-Pad1)") (class "Default")
      (node (ref "C36") (pin "1") (pinfunction "1_1") (pintype "passive"))
      (node (ref "R23") (pin "2") (pinfunction "2_2") (pintype "passive"))
      (node (ref "R25") (pin "1") (pinfunction "1_1") (pintype "passive"))
    )
    (net (code "46") (name "Net-(C36-Pad2)") (class "Default")
      (node (ref "C36") (pin "2") (pinfunction "2_2") (pintype "passive"))
      (node (ref "R27") (pin "2") (pinfunction "2_2") (pintype "passive"))
    )
    (net (code "47") (name "Net-(C70-Pad1)") (class "Default")
      (node (ref "C70") (pin "1") (pinfunction "1_1") (pintype "passive"))
      (node (ref "R70") (pin "2") (pinfunction "2_2") (pintype "passive"))
      (node (ref "R71") (pin "1") (pinfunction "1_1") (pintype "passive"))
    )
    (net (code "48") (name "Net-(D1-A)") (class "Default")
      (node (ref "D1") (pin "1") (pinfunction "A_1") (pintype "passive"))
      (node (ref "R5") (pin "1") (pinfunction "1_1") (pintype "passive"))
    )
    (net (code "49") (name "Net-(D2-A)") (class "Default")
      (node (ref "D2") (pin "1") (pinfunction "A_1") (pintype "passive"))
      (node (ref "R6") (pin "1") (pinfunction "1_1") (pintype "passive"))
    )
    (net (code "50") (name "Net-(D3-A)") (class "Default")
      (node (ref "D3") (pin "1") (pinfunction "A_1") (pintype "passive"))
      (node (ref "R7") (pin "1") (pinfunction "1_1") (pintype "passive"))
    )
    (net (code "51") (name "Net-(D4-K)") (class "Default")
      (node (ref "D4") (pin "1") (pinfunction "K_1") (pintype "passive"))
      (node (ref "D5") (pin "1") (pinfunction "K_1") (pintype "passive"))
      (node (ref "S2") (pin "3") (pinfunction "3_3") (pintype "passive"))
      (node (ref "S2") (pin "4") (pinfunction "4_4") (pintype "passive"))
    )
    (net (code "52") (name "Net-(P4-Pad2)") (class "Default")
      (node (ref "P4") (pin "2") (pinfunction "2_2") (pintype "passive"))
      (node (ref "R13") (pin "1") (pinfunction "1_1") (pintype "passive"))
    )
    (net (code "53") (name "Net-(P4-Pad3)") (class "Default")
      (node (ref "P4") (pin "3") (pinfunction "3_3") (pintype "passive"))
      (node (ref "R14") (pin "1") (pinfunction "1_1") (pintype "passive"))
    )
    (net (code "54") (name "Net-(Q8-D)") (class "Default")
      (node (ref "Q8") (pin "3") (pinfunction "D_3") (pintype "passive"))
      (node (ref "R27") (pin "1") (pinfunction "1_1") (pintype "passive"))
      (node (ref "R72") (pin "2") (pinfunction "2_2") (pintype "passive"))
    )
    (net (code "55") (name "Net-(U5_1-INT1)") (class "Default")
      (node (ref "R74") (pin "1") (pinfunction "1_1") (pintype "passive"))
      (node (ref "U5_1") (pin "5") (pinfunction "INT1_5") (pintype "passive"))
    )
    (net (code "56") (name "Net-(U5_1-INT2)") (class "Default")
      (node (ref "R73") (pin "1") (pinfunction "1_1") (pintype "passive"))
      (node (ref "U5_1") (pin "6") (pinfunction "INT2_6") (pintype "passive"))
    )
    (net (code "57") (name "Net-(U6-USB0_DM)") (class "Default")
      (node (ref "R13") (pin "2") (pinfunction "2_2") (pintype "passive"))
      (node (ref "U6") (pin "4") (pinfunction "USB0_DM_4") (pintype "passive"))
    )
    (net (code "58") (name "Net-(U6-USB0_DP)") (class "Default")
      (node (ref "R14") (pin "2") (pinfunction "2_2") (pintype "passive"))
      (node (ref "U6") (pin "3") (pinfunction "USB0_DP_3") (pintype "passive"))
    )
    (net (code "59") (name "Net-(U6-VOUT33)") (class "Default")
      (node (ref "C25") (pin "1") (pinfunction "1_1") (pintype "passive"))
      (node (ref "U6") (pin "5") (pinfunction "VOUT33_5") (pintype "passive"))
    )
    (net (code "60") (name "Net-(U6-VREFH)") (class "Default")
      (node (ref "C27") (pin "2") (pinfunction "2_2") (pintype "passive"))
      (node (ref "L3") (pin "1") (pinfunction "1_1") (pintype "passive"))
      (node (ref "U6") (pin "10") (pinfunction "VREFH_10") (pintype "passive"))
    )
    (net (code "61") (name "Net-(U6-VREGIN)") (class "Default")
      (node (ref "R16") (pin "1") (pinfunction "1_1") (pintype "passive"))
      (node (ref "U6") (pin "6") (pinfunction "VREGIN_6") (pintype "passive"))
    )
    (net (code "62") (name "Net-(U7-BYPASS)") (class "Default")
      (node (ref "C37") (pin "2") (pinfunction "2_2") (pintype "passive"))
      (node (ref "U7") (pin "2") (pinfunction "BYPASS_2") (pintype "input"))
    )
    (net (code "63") (name "Net-(U7-IN+)") (class "Default")
      (node (ref "R19") (pin "2") (pinfunction "2_2") (pintype "passive"))
      (node (ref "R21") (pin "1") (pinfunction "1_1") (pintype "passive"))
      (node (ref "U7") (pin "3") (pinfunction "IN+_3") (pintype "input"))
    )
    (net (code "64") (name "Net-(U7-IN-)") (class "Default")
      (node (ref "R18") (pin "2") (pinfunction "2_2") (pintype "passive"))
      (node (ref "R23") (pin "1") (pinfunction "1_1") (pintype "passive"))
      (node (ref "U7") (pin "4") (pinfunction "IN-_4") (pintype "input"))
    )
    (net (code "65") (name "Net-(U7-VO+)") (class "Default")
      (node (ref "P6") (pin "1") (pinfunction "1_1") (pintype "passive"))
      (node (ref "R18") (pin "1") (pinfunction "1_1") (pintype "passive"))
      (node (ref "R20") (pin "2") (pinfunction "2_2") (pintype "passive"))
      (node (ref "U7") (pin "5") (pinfunction "VO+_5") (pintype "output"))
    )
    (net (code "66") (name "Net-(U7-VO-)") (class "Default")
      (node (ref "P6") (pin "2") (pinfunction "2_2") (pintype "passive"))
      (node (ref "R19") (pin "1") (pinfunction "1_1") (pintype "passive"))
      (node (ref "U7") (pin "8") (pinfunction "VO-_8") (pintype "output"))
    )
    (net (code "67") (name "Vgsm") (class "Default")
      (node (ref "U7") (pin "6") (pinfunction "VDD_6") (pintype "power_in"))
    )
    (net (code "68") (name "unconnected-(U5-N{slash}C-Pad2)") (class "Default")
      (node (ref "U5") (pin "2") (pinfunction "N/C_2") (pintype "passive"))
    )
    (net (code "69") (name "unconnected-(U5-RES-Pad10)") (class "Default")
      (node (ref "U5") (pin "10") (pinfunction "RES_10") (pintype "passive"))
    )
    (net (code "70") (name "unconnected-(U5_1-CSB-Pad10)") (class "Default")
      (node (ref "U5_1") (pin "10") (pinfunction "CSB_10") (pintype "passive+no_connect"))
    )
    (net (code "71") (name "unconnected-(U5_2-INT2-Pad9)") (class "Default")
      (node (ref "U5_2") (pin "9") (pinfunction "INT2_9") (pintype "passive"))
    )
    (net (code "72") (name "unconnected-(U5_2-NC-Pad2)") (class "Default")
      (node (ref "U5_2") (pin "2") (pinfunction "NC_2") (pintype "passive"))
    )
    (net (code "73") (name "unconnected-(U5_2-NC-Pad15)") (class "Default")
      (node (ref "U5_2") (pin "15") (pinfunction "NC_15") (pintype "passive"))
    )
    (net (code "74") (name "unconnected-(U5_2-RES-Pad3)") (class "Default")
      (node (ref "U5_2") (pin "3") (pinfunction "RES_3") (pintype "passive"))
    )
    (net (code "75") (name "unconnected-(U5_2-RES-Pad5)") (class "Default")
      (node (ref "U5_2") (pin "5") (pinfunction "RES_5") (pintype "passive"))
    )
    (net (code "76") (name "unconnected-(U5_2-RES-Pad10)") (class "Default")
      (node (ref "U5_2") (pin "10") (pinfunction "RES_10") (pintype "passive"))
    )
    (net (code "77") (name "unconnected-(U6-NMI_b{slash}TSI0_CH5{slash}PTA4{slash}I2C1_SDA{slash}TPM0_CH1{slash}na{slash}na{slash}na{slash}NMI_b-Pad21)") (class "Default")
      (node (ref "U6") (pin "21") (pinfunction "NMI_b/TSI0_CH5/PTA4/I2C1_SDA/TPM0_CH1/na/na/na/NMI_b_21") (pintype "passive+no_connect"))
    )
  )
)
